# promini.net
KiCad netlist of a schematic drawn in EAGLE
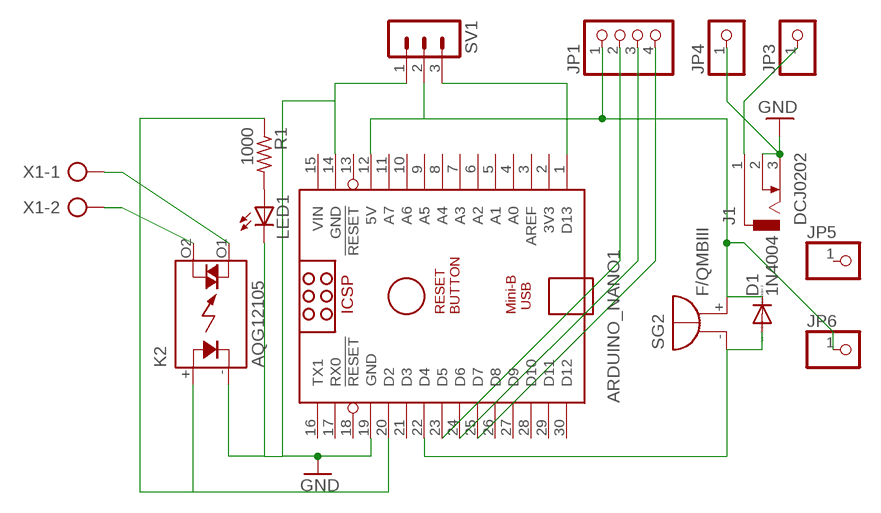
[diagram p0: schematic, sheet 1]

(export (version "E")
  (design (tool "Eeschema 10.0.6"))
  (components
    (comp (ref "ARDUINO_NANO1")
      (value "ARDUINO_NANO")
      (footprint "eagle-import:ARDUINO_NANO")
      (libsource (lib "eagle-import") (part "ARDUINO_NANO"))
    )
    (comp (ref "D1")
      (value "1N4004")
      (footprint "eagle-import:DO41-10")
      (libsource (lib "eagle-import") (part "1N4004"))
    )
    (comp (ref "J1")
      (value "DCJ0202")
      (footprint "eagle-import:DCJ0202")
      (libsource (lib "eagle-import") (part "DCJ0202"))
    )
    (comp (ref "JP1")
      (value "PINHD-1X4")
      (footprint "eagle-import:1X04")
      (libsource (lib "eagle-import") (part "PINHD-1X4"))
    )
    (comp (ref "JP3")
      (value "PINHD-1X1")
      (footprint "eagle-import:1X01")
      (libsource (lib "eagle-import") (part "PINHD-1X1"))
    )
    (comp (ref "JP4")
      (value "PINHD-1X1")
      (footprint "eagle-import:1X01")
      (libsource (lib "eagle-import") (part "PINHD-1X1"))
    )
    (comp (ref "JP5")
      (value "PINHD-1X1")
      (footprint "eagle-import:1X01")
      (libsource (lib "eagle-import") (part "PINHD-1X1"))
    )
    (comp (ref "JP6")
      (value "PINHD-1X1")
      (footprint "eagle-import:1X01")
      (libsource (lib "eagle-import") (part "PINHD-1X1"))
    )
    (comp (ref "K2")
      (value "AQG12105")
      (footprint "eagle-import:AQG")
      (fields (field (name "MF") "AROMAT/ MATSUSHITA"))
      (libsource (lib "eagle-import") (part "AQG12105"))
    )
    (comp (ref "LED1")
      (value "LED5MM")
      (footprint "eagle-import:LED5MM")
      (libsource (lib "eagle-import") (part "LED5MM"))
    )
    (comp (ref "R1")
      (value "1000")
      (footprint "eagle-import:0204_7")
      (libsource (lib "eagle-import") (part "R-US_0204/7"))
    )
    (comp (ref "SG2")
      (value "F/QMBIII")
      (footprint "eagle-import:F_QMBIII")
      (libsource (lib "eagle-import") (part "F/QMBIII"))
    )
    (comp (ref "SV1")
      (value "MA03-1")
      (footprint "eagle-import:MA03-1")
      (libsource (lib "eagle-import") (part "MA03-1"))
    )
    (comp (ref "X1")
      (value "AK300/2")
      (footprint "eagle-import:AK300_2")
      (libsource (lib "eagle-import") (part "AK300/2"))
    )
  )
  (nets
    (net (code "1") (name "/VIN") (class "Default")
      (node (ref "ARDUINO_NANO1") (pin "15") (pinfunction "VIN_15") (pintype "power_in"))
    )
    (net (code "2") (name "GND") (class "Default")
      (node (ref "ARDUINO_NANO1") (pin "14") (pinfunction "GND_14") (pintype "power_in"))
      (node (ref "ARDUINO_NANO1") (pin "19") (pinfunction "GND_19") (pintype "power_in"))
      (node (ref "J1") (pin "2") (pinfunction "2_2") (pintype "passive"))
      (node (ref "J1") (pin "3") (pinfunction "3_3") (pintype "passive"))
      (node (ref "JP4") (pin "1") (pinfunction "1_1") (pintype "passive"))
      (node (ref "K2") (pin "-") (pinfunction "K_-") (pintype "passive"))
      (node (ref "LED1") (pin "K") (pinfunction "C_K") (pintype "passive"))
      (node (ref "SV1") (pin "1") (pinfunction "1_1") (pintype "passive"))
    )
    (net (code "3") (name "Net-(ARDUINO_NANO1-5V)") (class "Default")
      (node (ref "ARDUINO_NANO1") (pin "12") (pinfunction "5V_12") (pintype "power_in"))
      (node (ref "D1") (pin "C") (pinfunction "C_C") (pintype "passive"))
      (node (ref "JP1") (pin "1") (pinfunction "1_1") (pintype "passive"))
      (node (ref "JP6") (pin "1") (pinfunction "1_1") (pintype "passive"))
      (node (ref "SG2") (pin "+") (pinfunction "-_+") (pintype "passive"))
      (node (ref "SV1") (pin "2") (pinfunction "2_2") (pintype "passive"))
    )
    (net (code "4") (name "Net-(ARDUINO_NANO1-D2)") (class "Default")
      (node (ref "ARDUINO_NANO1") (pin "20") (pinfunction "D2_20") (pintype "bidirectional"))
      (node (ref "K2") (pin "+") (pinfunction "A_+") (pintype "passive"))
      (node (ref "R1") (pin "1") (pinfunction "1_1") (pintype "passive"))
    )
    (net (code "5") (name "Net-(ARDUINO_NANO1-D4)") (class "Default")
      (node (ref "ARDUINO_NANO1") (pin "22") (pinfunction "D4_22") (pintype "bidirectional"))
      (node (ref "D1") (pin "A") (pinfunction "A_A") (pintype "passive"))
      (node (ref "SG2") (pin "-") (pinfunction "+_-") (pintype "passive"))
    )
    (net (code "6") (name "Net-(ARDUINO_NANO1-D5)") (class "Default")
      (node (ref "ARDUINO_NANO1") (pin "23") (pinfunction "D5_23") (pintype "bidirectional"))
      (node (ref "JP1") (pin "2") (pinfunction "2_2") (pintype "passive"))
    )
    (net (code "7") (name "Net-(ARDUINO_NANO1-D6)") (class "Default")
      (node (ref "ARDUINO_NANO1") (pin "24") (pinfunction "D6_24") (pintype "bidirectional"))
      (node (ref "JP1") (pin "3") (pinfunction "3_3") (pintype "passive"))
    )
    (net (code "8") (name "Net-(ARDUINO_NANO1-D7)") (class "Default")
      (node (ref "ARDUINO_NANO1") (pin "25") (pinfunction "D7_25") (pintype "bidirectional"))
      (node (ref "JP1") (pin "4") (pinfunction "4_4") (pintype "passive"))
    )
    (net (code "9") (name "Net-(ARDUINO_NANO1-D13)") (class "Default")
      (node (ref "ARDUINO_NANO1") (pin "1") (pinfunction "D13_1") (pintype "bidirectional"))
      (node (ref "SV1") (pin "3") (pinfunction "3_3") (pintype "passive"))
    )
    (net (code "10") (name "Net-(J1-Pad1)") (class "Default")
      (node (ref "J1") (pin "1") (pinfunction "1_1") (pintype "passive"))
      (node (ref "JP3") (pin "1") (pinfunction "1_1") (pintype "passive"))
    )
    (net (code "11") (name "Net-(K2-DS1)") (class "Default")
      (node (ref "K2") (pin "O2") (pinfunction "DS1_O2") (pintype "passive"))
      (node (ref "X1") (pin "2") (pinfunction "KL_2") (pintype "passive"))
    )
    (net (code "12") (name "Net-(K2-DS2)") (class "Default")
      (node (ref "K2") (pin "O1") (pinfunction "DS2_O1") (pintype "passive"))
      (node (ref "X1") (pin "1") (pinfunction "KL_1") (pintype "passive"))
    )
    (net (code "13") (name "Net-(LED1-PadA)") (class "Default")
      (node (ref "LED1") (pin "A") (pinfunction "A_A") (pintype "passive"))
      (node (ref "R1") (pin "2") (pinfunction "2_2") (pintype "passive"))
    )
    (net (code "14") (name "unconnected-(ARDUINO_NANO1-3V3-Pad2)") (class "Default")
      (node (ref "ARDUINO_NANO1") (pin "2") (pinfunction "3V3_2") (pintype "output"))
    )
    (net (code "15") (name "unconnected-(ARDUINO_NANO1-A0-Pad4)") (class "Default")
      (node (ref "ARDUINO_NANO1") (pin "4") (pinfunction "A0_4") (pintype "bidirectional"))
    )
    (net (code "16") (name "unconnected-(ARDUINO_NANO1-A1-Pad5)") (class "Default")
      (node (ref "ARDUINO_NANO1") (pin "5") (pinfunction "A1_5") (pintype "bidirectional"))
    )
    (net (code "17") (name "unconnected-(ARDUINO_NANO1-A2-Pad6)") (class "Default")
      (node (ref "ARDUINO_NANO1") (pin "6") (pinfunction "A2_6") (pintype "bidirectional"))
    )
    (net (code "18") (name "unconnected-(ARDUINO_NANO1-A3-Pad7)") (class "Default")
      (node (ref "ARDUINO_NANO1") (pin "7") (pinfunction "A3_7") (pintype "bidirectional"))
    )
    (net (code "19") (name "unconnected-(ARDUINO_NANO1-A4-Pad8)") (class "Default")
      (node (ref "ARDUINO_NANO1") (pin "8") (pinfunction "A4_8") (pintype "bidirectional"))
    )
    (net (code "20") (name "unconnected-(ARDUINO_NANO1-A5-Pad9)") (class "Default")
      (node (ref "ARDUINO_NANO1") (pin "9") (pinfunction "A5_9") (pintype "bidirectional"))
    )
    (net (code "21") (name "unconnected-(ARDUINO_NANO1-A6-Pad10)") (class "Default")
      (node (ref "ARDUINO_NANO1") (pin "10") (pinfunction "A6_10") (pintype "bidirectional"))
    )
    (net (code "22") (name "unconnected-(ARDUINO_NANO1-A7-Pad11)") (class "Default")
      (node (ref "ARDUINO_NANO1") (pin "11") (pinfunction "A7_11") (pintype "bidirectional"))
    )
    (net (code "23") (name "unconnected-(ARDUINO_NANO1-AREF-Pad3)") (class "Default")
      (node (ref "ARDUINO_NANO1") (pin "3") (pinfunction "AREF_3") (pintype "input"))
    )
    (net (code "24") (name "unconnected-(ARDUINO_NANO1-D3-Pad21)") (class "Default")
      (node (ref "ARDUINO_NANO1") (pin "21") (pinfunction "D3_21") (pintype "bidirectional"))
    )
    (net (code "25") (name "unconnected-(ARDUINO_NANO1-D8-Pad26)") (class "Default")
      (node (ref "ARDUINO_NANO1") (pin "26") (pinfunction "D8_26") (pintype "bidirectional"))
    )
    (net (code "26") (name "unconnected-(ARDUINO_NANO1-D9-Pad27)") (class "Default")
      (node (ref "ARDUINO_NANO1") (pin "27") (pinfunction "D9_27") (pintype "bidirectional"))
    )
    (net (code "27") (name "unconnected-(ARDUINO_NANO1-D10-Pad28)") (class "Default")
      (node (ref "ARDUINO_NANO1") (pin "28") (pinfunction "D10_28") (pintype "bidirectional"))
    )
    (net (code "28") (name "unconnected-(ARDUINO_NANO1-D11-Pad29)") (class "Default")
      (node (ref "ARDUINO_NANO1") (pin "29") (pinfunction "D11_29") (pintype "bidirectional"))
    )
    (net (code "29") (name "unconnected-(ARDUINO_NANO1-D12-Pad30)") (class "Default")
      (node (ref "ARDUINO_NANO1") (pin "30") (pinfunction "D12_30") (pintype "bidirectional"))
    )
    (net (code "30") (name "unconnected-(ARDUINO_NANO1-RX0-Pad17)") (class "Default")
      (node (ref "ARDUINO_NANO1") (pin "17") (pinfunction "RX0_17") (pintype "bidirectional"))
    )
    (net (code "31") (name "unconnected-(ARDUINO_NANO1-TX1-Pad16)") (class "Default")
      (node (ref "ARDUINO_NANO1") (pin "16") (pinfunction "TX1_16") (pintype "bidirectional"))
    )
    (net (code "32") (name "unconnected-(ARDUINO_NANO1-~{RESET}-Pad13)") (class "Default")
      (node (ref "ARDUINO_NANO1") (pin "13") (pinfunction "~{RESET}_13") (pintype "input"))
    )
    (net (code "33") (name "unconnected-(ARDUINO_NANO1-~{RESET}-Pad18)") (class "Default")
      (node (ref "ARDUINO_NANO1") (pin "18") (pinfunction "~{RESET}_18") (pintype "input"))
    )
    (net (code "34") (name "unconnected-(JP5-Pad1)") (class "Default")
      (node (ref "JP5") (pin "1") (pinfunction "1_1") (pintype "passive"))
    )
  )
)
